# uino-mx250.net
KiCad netlist of a schematic drawn in EAGLE
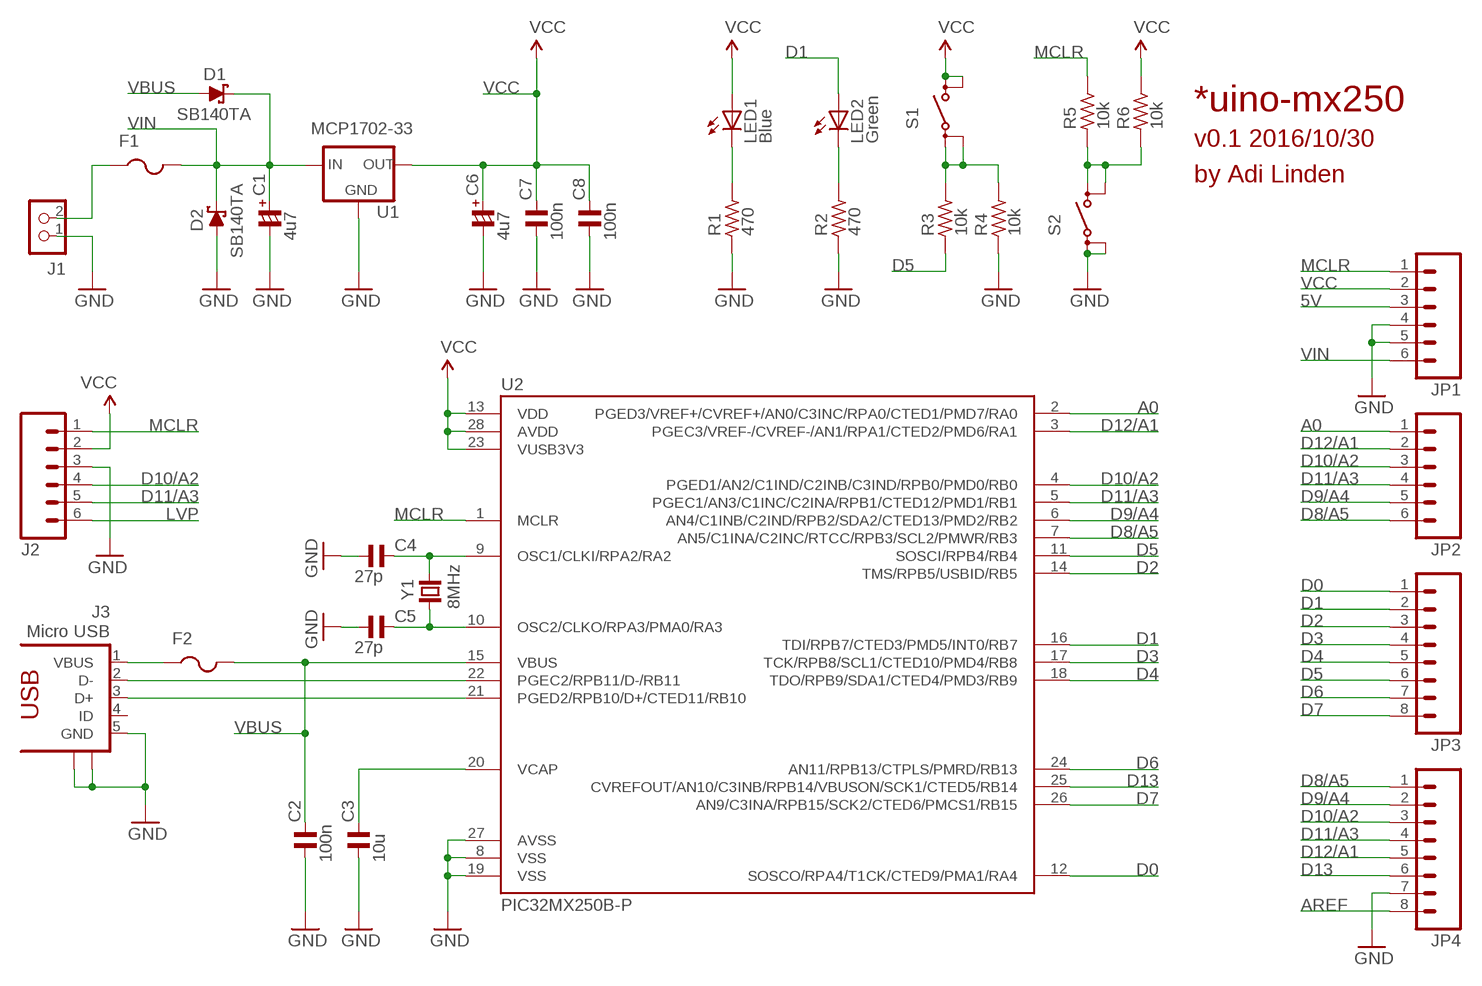
[diagram p0: schematic, sheet 1]

(export (version "E")
  (design (tool "Eeschema 10.0.6"))
  (components
    (comp (ref "C1")
      (value "4u7")
      (footprint "eagle-import:CTT-025-040")
      (libsource (lib "eagle-import") (part "CP_TT025-040"))
    )
    (comp (ref "C2")
      (value "100n")
      (footprint "eagle-import:C025-040X018")
      (libsource (lib "eagle-import") (part "C_C025-040X018"))
    )
    (comp (ref "C3")
      (value "10u")
      (footprint "eagle-import:C025-040X018")
      (libsource (lib "eagle-import") (part "C_C025-040X018"))
    )
    (comp (ref "C4")
      (value "27p")
      (footprint "eagle-import:C025-040X018")
      (libsource (lib "eagle-import") (part "C_C025-040X018"))
    )
    (comp (ref "C5")
      (value "27p")
      (footprint "eagle-import:C025-040X018")
      (libsource (lib "eagle-import") (part "C_C025-040X018"))
    )
    (comp (ref "C6")
      (value "4u7")
      (footprint "eagle-import:CTT-025-040")
      (libsource (lib "eagle-import") (part "CP_TT025-040"))
    )
    (comp (ref "C7")
      (value "100n")
      (footprint "eagle-import:C025-040X018")
      (libsource (lib "eagle-import") (part "C_C025-040X018"))
    )
    (comp (ref "C8")
      (value "100n")
      (footprint "eagle-import:C025-040X018")
      (libsource (lib "eagle-import") (part "C_C025-040X018"))
    )
    (comp (ref "D1")
      (value "SB140TA")
      (footprint "eagle-import:DO35-7")
      (libsource (lib "eagle-import") (part "SCHOTTKY-DIODEDO35-7"))
    )
    (comp (ref "D2")
      (value "SB140TA")
      (footprint "eagle-import:DO35-7")
      (libsource (lib "eagle-import") (part "SCHOTTKY-DIODEDO35-7"))
    )
    (comp (ref "F1")
      (value "FUSE_PTC-TH")
      (footprint "eagle-import:PTC")
      (libsource (lib "eagle-import") (part "FUSE_PTC-TH"))
    )
    (comp (ref "F2")
      (value "FUSE_PTC-TH")
      (footprint "eagle-import:PTC")
      (libsource (lib "eagle-import") (part "FUSE_PTC-TH"))
    )
    (comp (ref "J1")
      (value "CON_TERMINAL_BLOCK_02-5MM")
      (footprint "eagle-import:TERMINAL_BLOCK_2P_5")
      (libsource (lib "eagle-import") (part "CON_TERMINAL_BLOCK_02-5MM"))
    )
    (comp (ref "J2")
      (value "M06LOCK")
      (footprint "eagle-import:1X06_LOCK")
      (libsource (lib "eagle-import") (part "SparkFun-Connectors_M06LOCK"))
    )
    (comp (ref "J3")
      (value "Micro USB")
      (footprint "eagle-import:ZX62D-AB-5P8")
      (libsource (lib "eagle-import") (part "USB_MICRO_B_2.0-TH"))
    )
    (comp (ref "JP1")
      (value "M06SIP")
      (footprint "eagle-import:1X06")
      (libsource (lib "eagle-import") (part "M06SIP"))
    )
    (comp (ref "JP2")
      (value "M06SIP")
      (footprint "eagle-import:1X06")
      (libsource (lib "eagle-import") (part "M06SIP"))
    )
    (comp (ref "JP3")
      (value "M081X08")
      (footprint "eagle-import:1X08")
      (libsource (lib "eagle-import") (part "M081X08"))
    )
    (comp (ref "JP4")
      (value "M081X08")
      (footprint "eagle-import:1X08")
      (libsource (lib "eagle-import") (part "M081X08"))
    )
    (comp (ref "LED1")
      (value "Blue")
      (footprint "eagle-import:LED3MM")
      (libsource (lib "eagle-import") (part "LED3MM"))
    )
    (comp (ref "LED2")
      (value "Green")
      (footprint "eagle-import:LED3MM")
      (libsource (lib "eagle-import") (part "LED3MM"))
    )
    (comp (ref "R1")
      (value "470")
      (footprint "eagle-import:0207_7")
      (libsource (lib "eagle-import") (part "R_X0207/7"))
    )
    (comp (ref "R2")
      (value "470")
      (footprint "eagle-import:0207_7")
      (libsource (lib "eagle-import") (part "R_X0207/7"))
    )
    (comp (ref "R3")
      (value "10k")
      (footprint "eagle-import:0207_7")
      (libsource (lib "eagle-import") (part "R_X0207/7"))
    )
    (comp (ref "R4")
      (value "10k")
      (footprint "eagle-import:0207_7")
      (libsource (lib "eagle-import") (part "R_X0207/7"))
    )
    (comp (ref "R5")
      (value "10k")
      (footprint "eagle-import:0207_7")
      (libsource (lib "eagle-import") (part "R_X0207/7"))
    )
    (comp (ref "R6")
      (value "10k")
      (footprint "eagle-import:0207_7")
      (libsource (lib "eagle-import") (part "R_X0207/7"))
    )
    (comp (ref "S1")
      (value "TL1100X")
      (footprint "eagle-import:TL1100X")
      (libsource (lib "eagle-import") (part "TL1100X"))
    )
    (comp (ref "S2")
      (value "TL1100X")
      (footprint "eagle-import:TL1100X")
      (libsource (lib "eagle-import") (part "TL1100X"))
    )
    (comp (ref "U1")
      (value "MCP1702-33")
      (footprint "eagle-import:TO-92")
      (libsource (lib "eagle-import") (part "V_REG_MCP170X"))
    )
    (comp (ref "U2")
      (value "PIC32MX250B-P")
      (footprint "eagle-import:DIL28-3")
      (libsource (lib "eagle-import") (part "PIC32MX250B-P"))
    )
    (comp (ref "Y1")
      (value "8MHz")
      (footprint "eagle-import:HC49_S")
      (libsource (lib "eagle-import") (part "CRYTALHC49S"))
    )
  )
  (nets
    (net (code "1") (name "/5V") (class "Default")
      (node (ref "JP1") (pin "3") (pinfunction "3_3") (pintype "passive"))
    )
    (net (code "2") (name "/A0") (class "Default")
      (node (ref "JP2") (pin "1") (pinfunction "1_1") (pintype "passive"))
      (node (ref "U2") (pin "2") (pinfunction "PGED3/VREF+/CVREF+/AN0/C3INC/RPA0/CTED1/PMD7/RA0_2") (pintype "bidirectional"))
    )
    (net (code "3") (name "/AREF") (class "Default")
      (node (ref "JP4") (pin "8") (pinfunction "8_8") (pintype "passive"))
    )
    (net (code "4") (name "/D0") (class "Default")
      (node (ref "JP3") (pin "1") (pinfunction "1_1") (pintype "passive"))
      (node (ref "U2") (pin "12") (pinfunction "SOSCO/RPA4/T1CK/CTED9/PMA1/RA4_12") (pintype "bidirectional"))
    )
    (net (code "5") (name "/D1") (class "Default")
      (node (ref "JP3") (pin "2") (pinfunction "2_2") (pintype "passive"))
      (node (ref "LED2") (pin "A") (pinfunction "A_A") (pintype "passive"))
      (node (ref "U2") (pin "16") (pinfunction "TDI/RPB7/CTED3/PMD5/INT0/RB7_16") (pintype "bidirectional"))
    )
    (net (code "6") (name "/D2") (class "Default")
      (node (ref "JP3") (pin "3") (pinfunction "3_3") (pintype "passive"))
      (node (ref "U2") (pin "14") (pinfunction "TMS/RPB5/USBID/RB5_14") (pintype "bidirectional"))
    )
    (net (code "7") (name "/D3") (class "Default")
      (node (ref "JP3") (pin "4") (pinfunction "4_4") (pintype "passive"))
      (node (ref "U2") (pin "17") (pinfunction "TCK/RPB8/SCL1/CTED10/PMD4/RB8_17") (pintype "bidirectional"))
    )
    (net (code "8") (name "/D4") (class "Default")
      (node (ref "JP3") (pin "5") (pinfunction "5_5") (pintype "passive"))
      (node (ref "U2") (pin "18") (pinfunction "TDO/RPB9/SDA1/CTED4/PMD3/RB9_18") (pintype "bidirectional"))
    )
    (net (code "9") (name "/D5") (class "Default")
      (node (ref "JP3") (pin "6") (pinfunction "6_6") (pintype "passive"))
      (node (ref "R3") (pin "1") (pinfunction "1_1") (pintype "passive"))
      (node (ref "U2") (pin "11") (pinfunction "SOSCI/RPB4/RB4_11") (pintype "bidirectional"))
    )
    (net (code "10") (name "/D6") (class "Default")
      (node (ref "JP3") (pin "7") (pinfunction "7_7") (pintype "passive"))
      (node (ref "U2") (pin "24") (pinfunction "AN11/RPB13/CTPLS/PMRD/RB13_24") (pintype "bidirectional"))
    )
    (net (code "11") (name "/D7") (class "Default")
      (node (ref "JP3") (pin "8") (pinfunction "8_8") (pintype "passive"))
      (node (ref "U2") (pin "26") (pinfunction "AN9/C3INA/RPB15/SCK2/CTED6/PMCS1/RB15_26") (pintype "bidirectional"))
    )
    (net (code "12") (name "/D8{slash}A5") (class "Default")
      (node (ref "JP2") (pin "6") (pinfunction "6_6") (pintype "passive"))
      (node (ref "JP4") (pin "1") (pinfunction "1_1") (pintype "passive"))
      (node (ref "U2") (pin "7") (pinfunction "AN5/C1INA/C2INC/RTCC/RPB3/SCL2/PMWR/RB3_7") (pintype "bidirectional"))
    )
    (net (code "13") (name "/D9{slash}A4") (class "Default")
      (node (ref "JP2") (pin "5") (pinfunction "5_5") (pintype "passive"))
      (node (ref "JP4") (pin "2") (pinfunction "2_2") (pintype "passive"))
      (node (ref "U2") (pin "6") (pinfunction "AN4/C1INB/C2IND/RPB2/SDA2/CTED13/PMD2/RB2_6") (pintype "bidirectional"))
    )
    (net (code "14") (name "/D10{slash}A2") (class "Default")
      (node (ref "J2") (pin "4") (pinfunction "4_4") (pintype "passive"))
      (node (ref "JP2") (pin "3") (pinfunction "3_3") (pintype "passive"))
      (node (ref "JP4") (pin "3") (pinfunction "3_3") (pintype "passive"))
      (node (ref "U2") (pin "4") (pinfunction "PGED1/AN2/C1IND/C2INB/C3IND/RPB0/PMD0/RB0_4") (pintype "bidirectional"))
    )
    (net (code "15") (name "/D11{slash}A3") (class "Default")
      (node (ref "J2") (pin "5") (pinfunction "5_5") (pintype "passive"))
      (node (ref "JP2") (pin "4") (pinfunction "4_4") (pintype "passive"))
      (node (ref "JP4") (pin "4") (pinfunction "4_4") (pintype "passive"))
      (node (ref "U2") (pin "5") (pinfunction "PGEC1/AN3/C1INC/C2INA/RPB1/CTED12/PMD1/RB1_5") (pintype "bidirectional"))
    )
    (net (code "16") (name "/D12{slash}A1") (class "Default")
      (node (ref "JP2") (pin "2") (pinfunction "2_2") (pintype "passive"))
      (node (ref "JP4") (pin "5") (pinfunction "5_5") (pintype "passive"))
      (node (ref "U2") (pin "3") (pinfunction "PGEC3/VREF-/CVREF-/AN1/RPA1/CTED2/PMD6/RA1_3") (pintype "bidirectional"))
    )
    (net (code "17") (name "/D13") (class "Default")
      (node (ref "JP4") (pin "6") (pinfunction "6_6") (pintype "passive"))
      (node (ref "U2") (pin "25") (pinfunction "CVREFOUT/AN10/C3INB/RPB14/VBUSON/SCK1/CTED5/RB14_25") (pintype "bidirectional"))
    )
    (net (code "18") (name "/LVP") (class "Default")
      (node (ref "J2") (pin "6") (pinfunction "6_6") (pintype "passive"))
    )
    (net (code "19") (name "/MCLR") (class "Default")
      (node (ref "J2") (pin "1") (pinfunction "1_1") (pintype "passive"))
      (node (ref "JP1") (pin "1") (pinfunction "1_1") (pintype "passive"))
      (node (ref "R5") (pin "2") (pinfunction "2_2") (pintype "passive"))
      (node (ref "U2") (pin "1") (pinfunction "MCLR_1") (pintype "bidirectional"))
    )
    (net (code "20") (name "/VBUS") (class "Default")
      (node (ref "C2") (pin "2") (pinfunction "2_2") (pintype "passive"))
      (node (ref "D1") (pin "A") (pinfunction "A_A") (pintype "passive"))
      (node (ref "F2") (pin "P$2") (pinfunction "2_P$2") (pintype "passive"))
      (node (ref "U2") (pin "15") (pinfunction "VBUS_15") (pintype "bidirectional"))
    )
    (net (code "21") (name "/VIN") (class "Default")
      (node (ref "C1") (pin "+") (pinfunction "+_+") (pintype "passive"))
      (node (ref "D1") (pin "C") (pinfunction "C_C") (pintype "passive"))
      (node (ref "D2") (pin "C") (pinfunction "C_C") (pintype "passive"))
      (node (ref "F1") (pin "P$2") (pinfunction "2_P$2") (pintype "passive"))
      (node (ref "JP1") (pin "6") (pinfunction "6_6") (pintype "passive"))
      (node (ref "U1") (pin "2") (pinfunction "IN_2") (pintype "input"))
    )
    (net (code "22") (name "GND") (class "Default")
      (node (ref "C1") (pin "-") (pinfunction "-_-") (pintype "passive"))
      (node (ref "C2") (pin "1") (pinfunction "1_1") (pintype "passive"))
      (node (ref "C3") (pin "1") (pinfunction "1_1") (pintype "passive"))
      (node (ref "C4") (pin "1") (pinfunction "1_1") (pintype "passive"))
      (node (ref "C5") (pin "1") (pinfunction "1_1") (pintype "passive"))
      (node (ref "C6") (pin "-") (pinfunction "-_-") (pintype "passive"))
      (node (ref "C7") (pin "1") (pinfunction "1_1") (pintype "passive"))
      (node (ref "C8") (pin "1") (pinfunction "1_1") (pintype "passive"))
      (node (ref "D2") (pin "A") (pinfunction "A_A") (pintype "passive"))
      (node (ref "J1") (pin "1") (pinfunction "1_1") (pintype "passive"))
      (node (ref "J2") (pin "3") (pinfunction "3_3") (pintype "passive"))
      (node (ref "J3") (pin "5") (pinfunction "GND_5") (pintype "passive"))
      (node (ref "J3") (pin "S1") (pinfunction "S1_S1") (pintype "passive"))
      (node (ref "J3") (pin "S2") (pinfunction "S2_S2") (pintype "passive"))
      (node (ref "JP1") (pin "4") (pinfunction "4_4") (pintype "passive"))
      (node (ref "JP1") (pin "5") (pinfunction "5_5") (pintype "passive"))
      (node (ref "JP4") (pin "7") (pinfunction "7_7") (pintype "passive"))
      (node (ref "R1") (pin "1") (pinfunction "1_1") (pintype "passive"))
      (node (ref "R2") (pin "1") (pinfunction "1_1") (pintype "passive"))
      (node (ref "R4") (pin "1") (pinfunction "1_1") (pintype "passive"))
      (node (ref "S2") (pin "1") (pinfunction "P_1") (pintype "passive"))
      (node (ref "S2") (pin "2") (pinfunction "P1_2") (pintype "passive"))
      (node (ref "U1") (pin "1") (pinfunction "GND_1") (pintype "input"))
      (node (ref "U2") (pin "19") (pinfunction "VSS_19") (pintype "bidirectional"))
      (node (ref "U2") (pin "27") (pinfunction "AVSS_27") (pintype "bidirectional"))
      (node (ref "U2") (pin "8") (pinfunction "VSS_8") (pintype "bidirectional"))
    )
    (net (code "23") (name "Net-(F1-1)") (class "Default")
      (node (ref "F1") (pin "P$1") (pinfunction "1_P$1") (pintype "passive"))
      (node (ref "J1") (pin "2") (pinfunction "2_2") (pintype "passive"))
    )
    (net (code "24") (name "Net-(F2-1)") (class "Default")
      (node (ref "F2") (pin "P$1") (pinfunction "1_P$1") (pintype "passive"))
      (node (ref "J3") (pin "1") (pinfunction "VBUS_1") (pintype "passive"))
    )
    (net (code "25") (name "Net-(J3-D+)") (class "Default")
      (node (ref "J3") (pin "3") (pinfunction "D+_3") (pintype "passive"))
      (node (ref "U2") (pin "21") (pinfunction "PGED2/RPB10/D+/CTED11/RB10_21") (pintype "bidirectional"))
    )
    (net (code "26") (name "Net-(J3-D-)") (class "Default")
      (node (ref "J3") (pin "2") (pinfunction "D-_2") (pintype "passive"))
      (node (ref "U2") (pin "22") (pinfunction "PGEC2/RPB11/D-/RB11_22") (pintype "bidirectional"))
    )
    (net (code "27") (name "Net-(LED1-C)") (class "Default")
      (node (ref "LED1") (pin "K") (pinfunction "C_K") (pintype "passive"))
      (node (ref "R1") (pin "2") (pinfunction "2_2") (pintype "passive"))
    )
    (net (code "28") (name "Net-(LED2-C)") (class "Default")
      (node (ref "LED2") (pin "K") (pinfunction "C_K") (pintype "passive"))
      (node (ref "R2") (pin "2") (pinfunction "2_2") (pintype "passive"))
    )
    (net (code "29") (name "Net-(S1-P)") (class "Default")
      (node (ref "R3") (pin "2") (pinfunction "2_2") (pintype "passive"))
      (node (ref "R4") (pin "2") (pinfunction "2_2") (pintype "passive"))
      (node (ref "S1") (pin "1") (pinfunction "P_1") (pintype "passive"))
      (node (ref "S1") (pin "2") (pinfunction "P1_2") (pintype "passive"))
    )
    (net (code "30") (name "Net-(S2-S)") (class "Default")
      (node (ref "R5") (pin "1") (pinfunction "1_1") (pintype "passive"))
      (node (ref "R6") (pin "1") (pinfunction "1_1") (pintype "passive"))
      (node (ref "S2") (pin "3") (pinfunction "S_3") (pintype "passive"))
      (node (ref "S2") (pin "4") (pinfunction "S1_4") (pintype "passive"))
    )
    (net (code "31") (name "Net-(U2-OSC1{slash}CLKI{slash}RPA2{slash}RA2)") (class "Default")
      (node (ref "C4") (pin "2") (pinfunction "2_2") (pintype "passive"))
      (node (ref "U2") (pin "9") (pinfunction "OSC1/CLKI/RPA2/RA2_9") (pintype "bidirectional"))
      (node (ref "Y1") (pin "2") (pinfunction "2_2") (pintype "passive"))
    )
    (net (code "32") (name "Net-(U2-OSC2{slash}CLKO{slash}RPA3{slash}PMA0{slash}RA3)") (class "Default")
      (node (ref "C5") (pin "2") (pinfunction "2_2") (pintype "passive"))
      (node (ref "U2") (pin "10") (pinfunction "OSC2/CLKO/RPA3/PMA0/RA3_10") (pintype "bidirectional"))
      (node (ref "Y1") (pin "1") (pinfunction "1_1") (pintype "passive"))
    )
    (net (code "33") (name "Net-(U2-VCAP)") (class "Default")
      (node (ref "C3") (pin "2") (pinfunction "2_2") (pintype "passive"))
      (node (ref "U2") (pin "20") (pinfunction "VCAP_20") (pintype "bidirectional"))
    )
    (net (code "34") (name "VCC") (class "Default")
      (node (ref "C6") (pin "+") (pinfunction "+_+") (pintype "passive"))
      (node (ref "C7") (pin "2") (pinfunction "2_2") (pintype "passive"))
      (node (ref "C8") (pin "2") (pinfunction "2_2") (pintype "passive"))
      (node (ref "J2") (pin "2") (pinfunction "2_2") (pintype "passive"))
      (node (ref "JP1") (pin "2") (pinfunction "2_2") (pintype "passive"))
      (node (ref "LED1") (pin "A") (pinfunction "A_A") (pintype "passive"))
      (node (ref "R6") (pin "2") (pinfunction "2_2") (pintype "passive"))
      (node (ref "S1") (pin "3") (pinfunction "S_3") (pintype "passive"))
      (node (ref "S1") (pin "4") (pinfunction "S1_4") (pintype "passive"))
      (node (ref "U1") (pin "3") (pinfunction "OUT_3") (pintype "power_in"))
      (node (ref "U2") (pin "13") (pinfunction "VDD_13") (pintype "bidirectional"))
      (node (ref "U2") (pin "23") (pinfunction "VUSB3V3_23") (pintype "bidirectional"))
      (node (ref "U2") (pin "28") (pinfunction "AVDD_28") (pintype "bidirectional"))
    )
    (net (code "35") (name "unconnected-(J3-ID-Pad4)") (class "Default")
      (node (ref "J3") (pin "4") (pinfunction "ID_4") (pintype "passive"))
    )
  )
)
